# ProPrj_Iris_One_2026-02-21.net
KiCad netlist of a schematic drawn in EasyEDA Pro
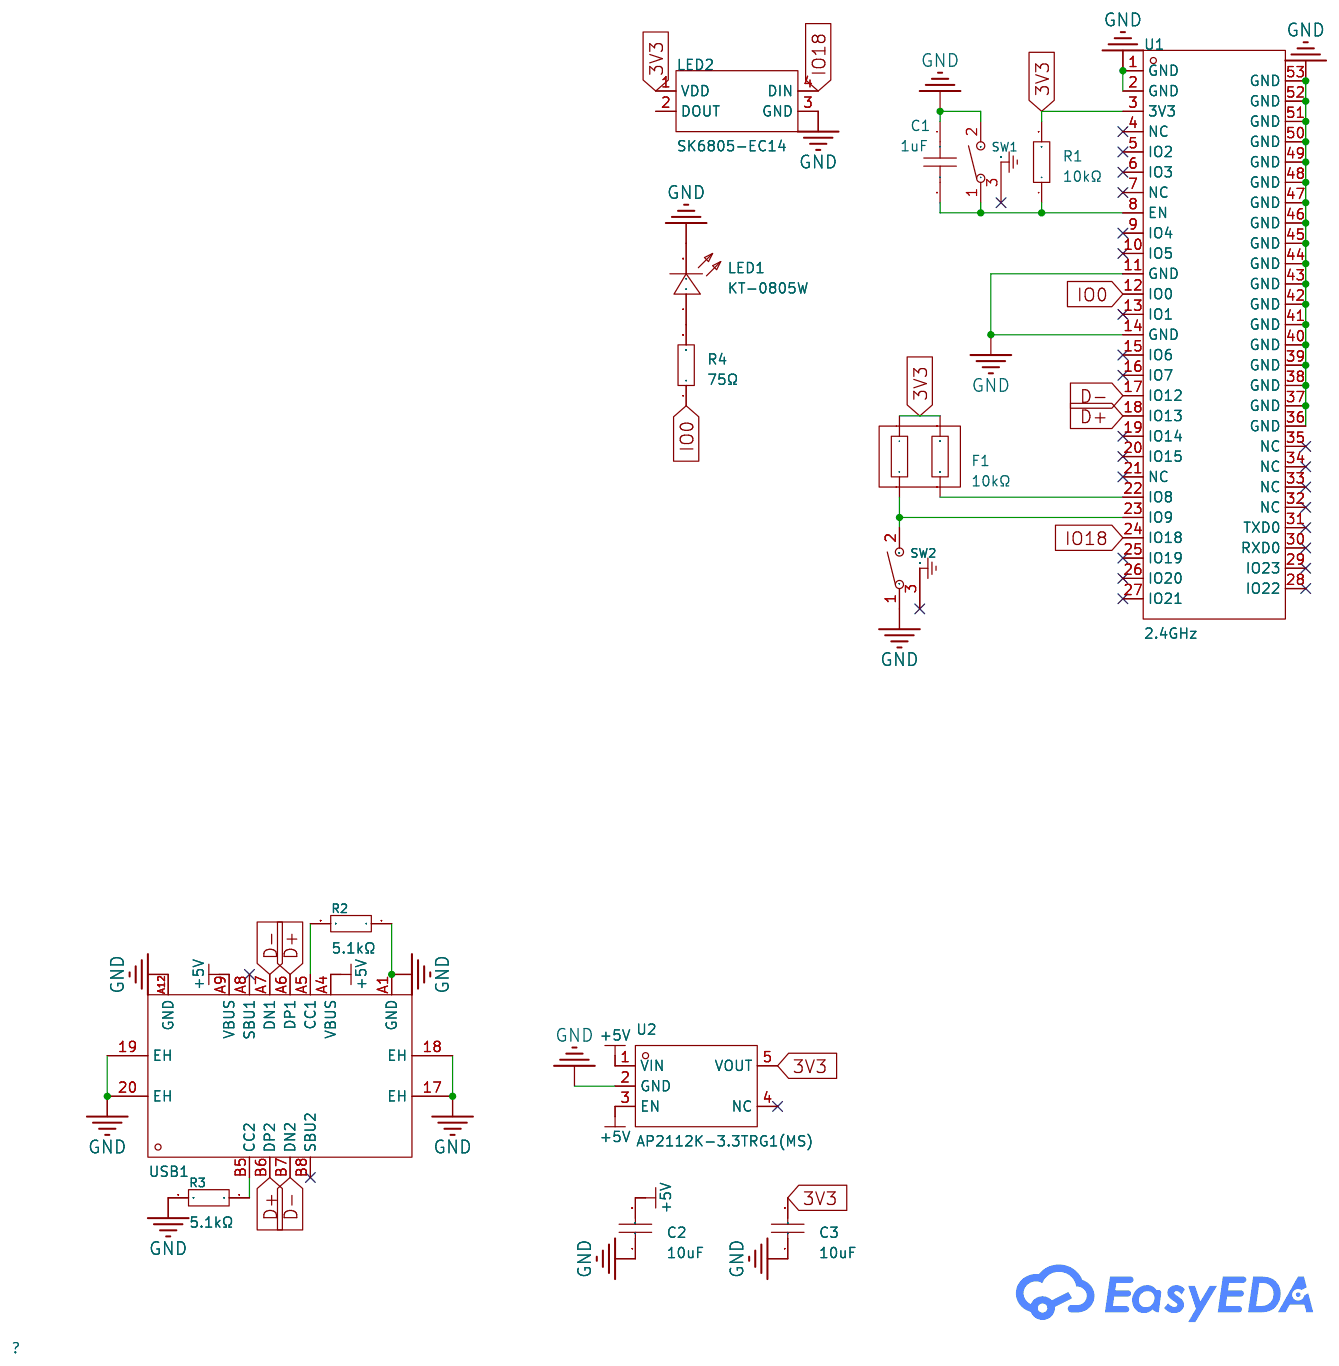
[diagram p0: schematic sheet]

(export (version "E")
  (design (tool "Eeschema 10.0.6"))
  (components
    (comp (ref "C1")
      (value "1uF")
      (footprint "easyedapro:C0402")
      (description "Capacitance:1uF Tolerance:±10% Tolerance:±10% Voltage Rating:25V Temperature Coefficient:X5R")
      (fields
        (field (name "Manufacturer Part") "CL05A105KA5NQNC")
        (field (name "Manufacturer") "SAMSUNG(三星)")
      )
      (libsource (lib "easyedapro") (part "CL05A105KA5NQNC"))
    )
    (comp (ref "C2")
      (value "10uF")
      (footprint "easyedapro:C0402")
      (description "Capacitance:10uF Tolerance:±20% Tolerance:±20% Voltage Rating:6.3V Temperature Coefficient:X5R")
      (fields
        (field (name "Manufacturer Part") "CL05A106MQ5NUNC")
        (field (name "Manufacturer") "SAMSUNG(三星)")
      )
      (libsource (lib "easyedapro") (part "CL05A106MQ5NUNC"))
    )
    (comp (ref "C3")
      (value "10uF")
      (footprint "easyedapro:C0402")
      (description "Capacitance:10uF Tolerance:±20% Tolerance:±20% Voltage Rating:6.3V Temperature Coefficient:X5R")
      (fields
        (field (name "Manufacturer Part") "CL05A106MQ5NUNC")
        (field (name "Manufacturer") "SAMSUNG(三星)")
      )
      (libsource (lib "easyedapro") (part "CL05A106MQ5NUNC"))
    )
    (comp (ref "F1")
      (value "10kΩ")
      (footprint "easyedapro:RES-ARRAY-SMD_0404-4P-L1.0-W1.0-BL")
      (fields (field (name "Manufacturer Part") "YC122-JR-0710KL") (field (name "Manufacturer") "YAGEO(国巨)"))
      (libsource (lib "easyedapro") (part "YC122-JR-0710KL"))
    )
    (comp (ref "LED1")
      (value "KT-0805W")
      (footprint "easyedapro:LED0805-R-RD")
      (fields (field (name "Manufacturer") "KENTO"))
      (libsource (lib "easyedapro") (part "whiteLEDSMD"))
    )
    (comp (ref "LED2")
      (value "SK6805-EC14")
      (footprint "easyedapro:LED-SMD_4P-L1.4-W1.4-TL")
      (fields (field (name "Manufacturer") "欧思科光电"))
      (libsource (lib "easyedapro") (part "SK6805-EC14_C2909055"))
    )
    (comp (ref "R1")
      (value "10kΩ")
      (footprint "easyedapro:R0402")
      (fields
        (field (name "Manufacturer Part") "0402WGF1002TCE")
        (field (name "Manufacturer") "UNI-ROYAL(厚声)")
      )
      (libsource (lib "easyedapro") (part "0402WGF1002TCE"))
    )
    (comp (ref "R2")
      (value "5.1kΩ")
      (footprint "easyedapro:R0402")
      (fields
        (field (name "Manufacturer Part") "0402WGF5101TCE")
        (field (name "Manufacturer") "UNI-ROYAL(厚声)")
      )
      (libsource (lib "easyedapro") (part "0402WGF5101TCE"))
    )
    (comp (ref "R3")
      (value "5.1kΩ")
      (footprint "easyedapro:R0402")
      (fields
        (field (name "Manufacturer Part") "0402WGF5101TCE")
        (field (name "Manufacturer") "UNI-ROYAL(厚声)")
      )
      (libsource (lib "easyedapro") (part "0402WGF5101TCE"))
    )
    (comp (ref "R4")
      (value "75Ω")
      (footprint "easyedapro:R0402")
      (fields
        (field (name "Manufacturer Part") "0402WGF750JTCE")
        (field (name "Manufacturer") "UNI-ROYAL(厚声)")
      )
      (libsource (lib "easyedapro") (part "0402WGF750JTCE"))
    )
    (comp (ref "SW1")
      (value "SKTDLHE010")
      (footprint "easyedapro:KEY-SMD_SKTDLHE010")
      (description "Circuit:SPST Actuator Style:Rectangle button Mounting Style:卧贴 With Lamp:- Mechanical Life:-")
      (fields (field (name "Manufacturer") "ALPSALPINE(阿尔卑斯阿尔派)"))
      (libsource (lib "easyedapro") (part "SKTDLHE010"))
    )
    (comp (ref "SW2")
      (value "SKTDLHE010")
      (footprint "easyedapro:KEY-SMD_SKTDLHE010")
      (description "Circuit:SPST Actuator Style:Rectangle button Mounting Style:卧贴 With Lamp:- Mechanical Life:-")
      (fields (field (name "Manufacturer") "ALPSALPINE(阿尔卑斯阿尔派)"))
      (libsource (lib "easyedapro") (part "SKTDLHE010"))
    )
    (comp (ref "U1")
      (value "2.4GHz")
      (footprint "easyedapro:WIFIM-SMD_61P-L16.6-W13.2-P0.80-ESP32-C6-MINI-1-N4")
      (fields
        (field (name "Manufacturer Part") "ESP32-C6-MINI-1-N4")
        (field (name "Manufacturer") "ESPRESSIF(乐鑫)")
      )
      (libsource (lib "easyedapro") (part "ESP32-C6-MINI-1-N4"))
    )
    (comp (ref "U2")
      (value "AP2112K-3.3TRG1(MS)")
      (footprint "easyedapro:SOT-23-5_L2.9-W1.6-P0.95-LS2.7-BR")
      (fields (field (name "Manufacturer") "MSKSEMI(美森科)"))
      (libsource (lib "easyedapro") (part "AP2112K-3.3TRG1(MS)"))
    )
    (comp (ref "USB1")
      (value "TYPE-C 16P QTGM027")
      (footprint "easyedapro:USB-C-SMD_TYPE-C-16P-QTGM027")
      (fields (field (name "Manufacturer") "SHOU HAN(首韩)"))
      (libsource (lib "easyedapro") (part "TYPE-C 16P QTGM027"))
    )
  )
  (nets
    (net (code "1") (name "+5V") (class "Default")
      (node (ref "C2") (pin "2") (pinfunction "2_2") (pintype "input"))
      (node (ref "U2") (pin "1") (pinfunction "VIN_1") (pintype "unspecified"))
      (node (ref "U2") (pin "3") (pinfunction "EN_3") (pintype "unspecified"))
      (node (ref "USB1") (pin "A4") (pinfunction "VBUS_A4") (pintype "unspecified"))
      (node (ref "USB1") (pin "A9") (pinfunction "VBUS_A9") (pintype "unspecified"))
    )
    (net (code "2") (name "3V3") (class "Default")
      (node (ref "C3") (pin "2") (pinfunction "2_2") (pintype "input"))
      (node (ref "F1") (pin "3") (pinfunction "3_3") (pintype "unspecified"))
      (node (ref "F1") (pin "4") (pinfunction "4_4") (pintype "unspecified"))
      (node (ref "LED2") (pin "1") (pinfunction "VDD_1") (pintype "unspecified"))
      (node (ref "R1") (pin "2") (pinfunction "2_2") (pintype "input"))
      (node (ref "U1") (pin "3") (pinfunction "3V3_3") (pintype "unspecified"))
      (node (ref "U2") (pin "5") (pinfunction "VOUT_5") (pintype "unspecified"))
    )
    (net (code "3") (name "D+") (class "Default")
      (node (ref "U1") (pin "18") (pinfunction "IO13_18") (pintype "unspecified"))
      (node (ref "USB1") (pin "A6") (pinfunction "DP1_A6") (pintype "unspecified"))
      (node (ref "USB1") (pin "B6") (pinfunction "DP2_B6") (pintype "unspecified"))
    )
    (net (code "4") (name "D-") (class "Default")
      (node (ref "U1") (pin "17") (pinfunction "IO12_17") (pintype "unspecified"))
      (node (ref "USB1") (pin "A7") (pinfunction "DN1_A7") (pintype "unspecified"))
      (node (ref "USB1") (pin "B7") (pinfunction "DN2_B7") (pintype "unspecified"))
    )
    (net (code "5") (name "GND") (class "Default")
      (node (ref "C1") (pin "1") (pinfunction "1_1") (pintype "unspecified"))
      (node (ref "C2") (pin "1") (pinfunction "1_1") (pintype "input"))
      (node (ref "C3") (pin "1") (pinfunction "1_1") (pintype "input"))
      (node (ref "LED1") (pin "2") (pinfunction "K_2") (pintype "unspecified"))
      (node (ref "LED2") (pin "3") (pinfunction "GND_3") (pintype "unspecified"))
      (node (ref "R2") (pin "1") (pinfunction "1_1") (pintype "input"))
      (node (ref "R3") (pin "2") (pinfunction "2_2") (pintype "input"))
      (node (ref "SW1") (pin "2") (pinfunction "2_2") (pintype "input"))
      (node (ref "SW2") (pin "1") (pinfunction "1_1") (pintype "input"))
      (node (ref "U1") (pin "1") (pinfunction "GND_1") (pintype "unspecified"))
      (node (ref "U1") (pin "11") (pinfunction "GND_11") (pintype "unspecified"))
      (node (ref "U1") (pin "14") (pinfunction "GND_14") (pintype "unspecified"))
      (node (ref "U1") (pin "2") (pinfunction "GND_2") (pintype "unspecified"))
      (node (ref "U1") (pin "36") (pinfunction "GND_36") (pintype "unspecified"))
      (node (ref "U1") (pin "37") (pinfunction "GND_37") (pintype "unspecified"))
      (node (ref "U1") (pin "38") (pinfunction "GND_38") (pintype "unspecified"))
      (node (ref "U1") (pin "39") (pinfunction "GND_39") (pintype "unspecified"))
      (node (ref "U1") (pin "40") (pinfunction "GND_40") (pintype "unspecified"))
      (node (ref "U1") (pin "41") (pinfunction "GND_41") (pintype "unspecified"))
      (node (ref "U1") (pin "42") (pinfunction "GND_42") (pintype "unspecified"))
      (node (ref "U1") (pin "43") (pinfunction "GND_43") (pintype "unspecified"))
      (node (ref "U1") (pin "44") (pinfunction "GND_44") (pintype "unspecified"))
      (node (ref "U1") (pin "45") (pinfunction "GND_45") (pintype "unspecified"))
      (node (ref "U1") (pin "46") (pinfunction "GND_46") (pintype "unspecified"))
      (node (ref "U1") (pin "47") (pinfunction "GND_47") (pintype "unspecified"))
      (node (ref "U1") (pin "48") (pinfunction "GND_48") (pintype "unspecified"))
      (node (ref "U1") (pin "49") (pinfunction "GND_49") (pintype "unspecified"))
      (node (ref "U1") (pin "50") (pinfunction "GND_50") (pintype "unspecified"))
      (node (ref "U1") (pin "51") (pinfunction "GND_51") (pintype "unspecified"))
      (node (ref "U1") (pin "52") (pinfunction "GND_52") (pintype "unspecified"))
      (node (ref "U1") (pin "53") (pinfunction "GND_53") (pintype "unspecified"))
      (node (ref "U2") (pin "2") (pinfunction "GND_2") (pintype "unspecified"))
      (node (ref "USB1") (pin "17") (pinfunction "EH_17") (pintype "unspecified"))
      (node (ref "USB1") (pin "18") (pinfunction "EH_18") (pintype "unspecified"))
      (node (ref "USB1") (pin "19") (pinfunction "EH_19") (pintype "unspecified"))
      (node (ref "USB1") (pin "20") (pinfunction "EH_20") (pintype "unspecified"))
      (node (ref "USB1") (pin "A1") (pinfunction "GND_A1") (pintype "unspecified"))
      (node (ref "USB1") (pin "A12") (pinfunction "GND_A12") (pintype "unspecified"))
    )
    (net (code "6") (name "IO0") (class "Default")
      (node (ref "R4") (pin "1") (pinfunction "1_1") (pintype "input"))
      (node (ref "U1") (pin "12") (pinfunction "IO0_12") (pintype "unspecified"))
    )
    (net (code "7") (name "IO18") (class "Default")
      (node (ref "LED2") (pin "4") (pinfunction "DIN_4") (pintype "unspecified"))
      (node (ref "U1") (pin "24") (pinfunction "IO18_24") (pintype "unspecified"))
    )
    (net (code "8") (name "Net-(LED1-A)") (class "Default")
      (node (ref "LED1") (pin "1") (pinfunction "A_1") (pintype "unspecified"))
      (node (ref "R4") (pin "2") (pinfunction "2_2") (pintype "input"))
    )
    (net (code "9") (name "Net-(U1-EN)") (class "Default")
      (node (ref "C1") (pin "2") (pinfunction "2_2") (pintype "unspecified"))
      (node (ref "R1") (pin "1") (pinfunction "1_1") (pintype "input"))
      (node (ref "SW1") (pin "1") (pinfunction "1_1") (pintype "input"))
      (node (ref "U1") (pin "8") (pinfunction "EN_8") (pintype "unspecified"))
    )
    (net (code "10") (name "Net-(U1-IO8)") (class "Default")
      (node (ref "F1") (pin "2") (pinfunction "2_2") (pintype "unspecified"))
      (node (ref "U1") (pin "22") (pinfunction "IO8_22") (pintype "unspecified"))
    )
    (net (code "11") (name "Net-(U1-IO9)") (class "Default")
      (node (ref "F1") (pin "1") (pinfunction "1_1") (pintype "unspecified"))
      (node (ref "SW2") (pin "2") (pinfunction "2_2") (pintype "input"))
      (node (ref "U1") (pin "23") (pinfunction "IO9_23") (pintype "unspecified"))
    )
    (net (code "12") (name "Net-(USB1-CC1)") (class "Default")
      (node (ref "R2") (pin "2") (pinfunction "2_2") (pintype "input"))
      (node (ref "USB1") (pin "A5") (pinfunction "CC1_A5") (pintype "unspecified"))
    )
    (net (code "13") (name "Net-(USB1-CC2)") (class "Default")
      (node (ref "R3") (pin "1") (pinfunction "1_1") (pintype "input"))
      (node (ref "USB1") (pin "B5") (pinfunction "CC2_B5") (pintype "unspecified"))
    )
    (net (code "14") (name "unconnected-(LED2-DOUT-Pad2)") (class "Default")
      (node (ref "LED2") (pin "2") (pinfunction "DOUT_2") (pintype "unspecified"))
    )
    (net (code "15") (name "unconnected-(SW1-GND-Pad3)") (class "Default")
      (node (ref "SW1") (pin "3") (pinfunction "GND_3") (pintype "input+no_connect"))
    )
    (net (code "16") (name "unconnected-(SW2-GND-Pad3)") (class "Default")
      (node (ref "SW2") (pin "3") (pinfunction "GND_3") (pintype "input+no_connect"))
    )
    (net (code "17") (name "unconnected-(U1-IO1-Pad13)") (class "Default")
      (node (ref "U1") (pin "13") (pinfunction "IO1_13") (pintype "unspecified+no_connect"))
    )
    (net (code "18") (name "unconnected-(U1-IO2-Pad5)") (class "Default")
      (node (ref "U1") (pin "5") (pinfunction "IO2_5") (pintype "unspecified+no_connect"))
    )
    (net (code "19") (name "unconnected-(U1-IO3-Pad6)") (class "Default")
      (node (ref "U1") (pin "6") (pinfunction "IO3_6") (pintype "unspecified+no_connect"))
    )
    (net (code "20") (name "unconnected-(U1-IO4-Pad9)") (class "Default")
      (node (ref "U1") (pin "9") (pinfunction "IO4_9") (pintype "unspecified+no_connect"))
    )
    (net (code "21") (name "unconnected-(U1-IO5-Pad10)") (class "Default")
      (node (ref "U1") (pin "10") (pinfunction "IO5_10") (pintype "unspecified+no_connect"))
    )
    (net (code "22") (name "unconnected-(U1-IO6-Pad15)") (class "Default")
      (node (ref "U1") (pin "15") (pinfunction "IO6_15") (pintype "unspecified+no_connect"))
    )
    (net (code "23") (name "unconnected-(U1-IO7-Pad16)") (class "Default")
      (node (ref "U1") (pin "16") (pinfunction "IO7_16") (pintype "unspecified+no_connect"))
    )
    (net (code "24") (name "unconnected-(U1-IO14-Pad19)") (class "Default")
      (node (ref "U1") (pin "19") (pinfunction "IO14_19") (pintype "unspecified+no_connect"))
    )
    (net (code "25") (name "unconnected-(U1-IO15-Pad20)") (class "Default")
      (node (ref "U1") (pin "20") (pinfunction "IO15_20") (pintype "unspecified+no_connect"))
    )
    (net (code "26") (name "unconnected-(U1-IO19-Pad25)") (class "Default")
      (node (ref "U1") (pin "25") (pinfunction "IO19_25") (pintype "unspecified+no_connect"))
    )
    (net (code "27") (name "unconnected-(U1-IO20-Pad26)") (class "Default")
      (node (ref "U1") (pin "26") (pinfunction "IO20_26") (pintype "unspecified+no_connect"))
    )
    (net (code "28") (name "unconnected-(U1-IO21-Pad27)") (class "Default")
      (node (ref "U1") (pin "27") (pinfunction "IO21_27") (pintype "unspecified+no_connect"))
    )
    (net (code "29") (name "unconnected-(U1-IO22-Pad28)") (class "Default")
      (node (ref "U1") (pin "28") (pinfunction "IO22_28") (pintype "unspecified+no_connect"))
    )
    (net (code "30") (name "unconnected-(U1-IO23-Pad29)") (class "Default")
      (node (ref "U1") (pin "29") (pinfunction "IO23_29") (pintype "unspecified+no_connect"))
    )
    (net (code "31") (name "unconnected-(U1-NC-Pad4)") (class "Default")
      (node (ref "U1") (pin "4") (pinfunction "NC_4") (pintype "unspecified+no_connect"))
    )
    (net (code "32") (name "unconnected-(U1-NC-Pad7)") (class "Default")
      (node (ref "U1") (pin "7") (pinfunction "NC_7") (pintype "unspecified+no_connect"))
    )
    (net (code "33") (name "unconnected-(U1-NC-Pad21)") (class "Default")
      (node (ref "U1") (pin "21") (pinfunction "NC_21") (pintype "unspecified+no_connect"))
    )
    (net (code "34") (name "unconnected-(U1-NC-Pad32)") (class "Default")
      (node (ref "U1") (pin "32") (pinfunction "NC_32") (pintype "unspecified+no_connect"))
    )
    (net (code "35") (name "unconnected-(U1-NC-Pad33)") (class "Default")
      (node (ref "U1") (pin "33") (pinfunction "NC_33") (pintype "unspecified+no_connect"))
    )
    (net (code "36") (name "unconnected-(U1-NC-Pad34)") (class "Default")
      (node (ref "U1") (pin "34") (pinfunction "NC_34") (pintype "unspecified+no_connect"))
    )
    (net (code "37") (name "unconnected-(U1-NC-Pad35)") (class "Default")
      (node (ref "U1") (pin "35") (pinfunction "NC_35") (pintype "unspecified+no_connect"))
    )
    (net (code "38") (name "unconnected-(U1-RXD0-Pad30)") (class "Default")
      (node (ref "U1") (pin "30") (pinfunction "RXD0_30") (pintype "unspecified+no_connect"))
    )
    (net (code "39") (name "unconnected-(U1-TXD0-Pad31)") (class "Default")
      (node (ref "U1") (pin "31") (pinfunction "TXD0_31") (pintype "unspecified+no_connect"))
    )
    (net (code "40") (name "unconnected-(U2-NC-Pad4)") (class "Default")
      (node (ref "U2") (pin "4") (pinfunction "NC_4") (pintype "unspecified+no_connect"))
    )
    (net (code "41") (name "unconnected-(USB1-SBU1-PadA8)") (class "Default")
      (node (ref "USB1") (pin "A8") (pinfunction "SBU1_A8") (pintype "unspecified+no_connect"))
    )
    (net (code "42") (name "unconnected-(USB1-SBU2-PadB8)") (class "Default")
      (node (ref "USB1") (pin "B8") (pinfunction "SBU2_B8") (pintype "unspecified+no_connect"))
    )
  )
)
